# Gausss_pincond.net
KiCad netlist of a schematic drawn in EAGLE
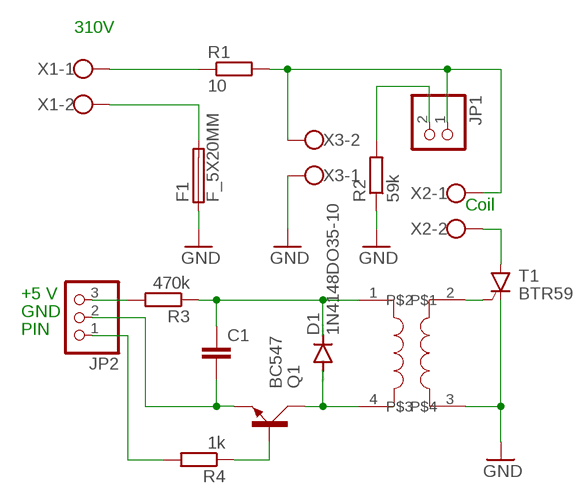
[diagram p0: schematic, sheet 1]

(export (version "E")
  (design (tool "Eeschema 10.0.6"))
  (components
    (comp (ref "C1")
      (value "C-EU025-025X050")
      (footprint "eagle-import:C025-025X050")
      (libsource (lib "eagle-import") (part "C-EU025-025X050"))
    )
    (comp (ref "D1")
      (value "1N4148DO35-10")
      (footprint "eagle-import:DO35-10")
      (libsource (lib "eagle-import") (part "1N4148DO35-10"))
    )
    (comp (ref "F1")
      (value "F_5X20MM")
      (footprint "eagle-import:FUSE_HOLDER_5X20MM")
      (libsource (lib "eagle-import") (part "FUSEBLANK_5X20MM"))
    )
    (comp (ref "JP1")
      (value "PINHD-1X2")
      (footprint "eagle-import:1X02")
      (libsource (lib "eagle-import") (part "PINHD-1X2"))
    )
    (comp (ref "JP2")
      (value "PINHD-1X3")
      (footprint "eagle-import:1X03")
      (libsource (lib "eagle-import") (part "PINHD-1X3"))
    )
    (comp (ref "Q1")
      (value "BC547")
      (footprint "eagle-import:SOT54A")
      (libsource (lib "eagle-import") (part "BC547"))
    )
    (comp (ref "R1")
      (value "10")
      (footprint "eagle-import:0207_10")
      (libsource (lib "eagle-import") (part "R-EU_0207/10"))
    )
    (comp (ref "R2")
      (value "59k")
      (footprint "eagle-import:0207_10")
      (libsource (lib "eagle-import") (part "R-EU_0207/10"))
    )
    (comp (ref "R3")
      (value "470k")
      (footprint "eagle-import:0207_10")
      (libsource (lib "eagle-import") (part "R-EU_0207/10"))
    )
    (comp (ref "R4")
      (value "1k")
      (footprint "eagle-import:0207_10")
      (libsource (lib "eagle-import") (part "R-EU_0207/10"))
    )
    (comp (ref "T1")
      (value "BTR59")
      (footprint "eagle-import:SOT93S")
      (libsource (lib "eagle-import") (part "BTR59"))
    )
    (comp (ref "U$2") (value "T") (footprint "eagle-import:SK11") (libsource (lib "eagle-import") (part "T")))
    (comp (ref "X1")
      (value "W237-102")
      (footprint "eagle-import:W237-102")
      (fields (field (name "MPN") "237-102"))
      (libsource (lib "eagle-import") (part "W237-102"))
    )
    (comp (ref "X2")
      (value "W237-102")
      (footprint "eagle-import:W237-102")
      (fields (field (name "MPN") "237-102"))
      (libsource (lib "eagle-import") (part "W237-102"))
    )
    (comp (ref "X3")
      (value "W237-102")
      (footprint "eagle-import:W237-102")
      (fields (field (name "MPN") "237-102"))
      (libsource (lib "eagle-import") (part "W237-102"))
    )
  )
  (nets
    (net (code "1") (name "GND") (class "Default")
      (node (ref "F1") (pin "1") (pinfunction "1_1") (pintype "passive"))
      (node (ref "R2") (pin "1") (pinfunction "1_1") (pintype "passive"))
      (node (ref "T1") (pin "C") (pinfunction "C_C") (pintype "passive"))
      (node (ref "U$2") (pin "3") (pinfunction "P$3_3") (pintype "bidirectional"))
      (node (ref "X3") (pin "1") (pinfunction "KL_1") (pintype "passive"))
    )
    (net (code "2") (name "Net-(C1-Pad2)") (class "Default")
      (node (ref "C1") (pin "2") (pinfunction "2_2") (pintype "passive"))
      (node (ref "JP2") (pin "2") (pinfunction "2_2") (pintype "passive"))
      (node (ref "Q1") (pin "E") (pinfunction "E_E") (pintype "passive"))
    )
    (net (code "3") (name "Net-(JP1-Pad2)") (class "Default")
      (node (ref "JP1") (pin "2") (pinfunction "2_2") (pintype "passive"))
      (node (ref "R2") (pin "2") (pinfunction "2_2") (pintype "passive"))
    )
    (net (code "4") (name "Net-(JP2-Pad1)") (class "Default")
      (node (ref "JP2") (pin "1") (pinfunction "1_1") (pintype "passive"))
      (node (ref "R4") (pin "2") (pinfunction "2_2") (pintype "passive"))
    )
    (net (code "5") (name "Net-(JP2-Pad3)") (class "Default")
      (node (ref "JP2") (pin "3") (pinfunction "3_3") (pintype "passive"))
      (node (ref "R3") (pin "2") (pinfunction "2_2") (pintype "passive"))
    )
    (net (code "6") (name "Net-(Q1-PadB)") (class "Default")
      (node (ref "Q1") (pin "B") (pinfunction "B_B") (pintype "passive"))
      (node (ref "R4") (pin "1") (pinfunction "1_1") (pintype "passive"))
    )
    (net (code "7") (name "Net-(U$2-P$1)") (class "Default")
      (node (ref "C1") (pin "1") (pinfunction "1_1") (pintype "passive"))
      (node (ref "D1") (pin "C") (pinfunction "C_C") (pintype "passive"))
      (node (ref "R3") (pin "1") (pinfunction "1_1") (pintype "passive"))
      (node (ref "U$2") (pin "1") (pinfunction "P$1_1") (pintype "bidirectional"))
    )
    (net (code "8") (name "Net-(U$2-P$2)") (class "Default")
      (node (ref "T1") (pin "G") (pinfunction "G_G") (pintype "passive"))
      (node (ref "U$2") (pin "2") (pinfunction "P$2_2") (pintype "bidirectional"))
    )
    (net (code "9") (name "Net-(U$2-P$4)") (class "Default")
      (node (ref "D1") (pin "A") (pinfunction "A_A") (pintype "passive"))
      (node (ref "Q1") (pin "C") (pinfunction "C_C") (pintype "passive"))
      (node (ref "U$2") (pin "4") (pinfunction "P$4_4") (pintype "bidirectional"))
    )
    (net (code "10") (name "Net-(X1A-KL)") (class "Default")
      (node (ref "R1") (pin "1") (pinfunction "1_1") (pintype "passive"))
      (node (ref "X1") (pin "1") (pinfunction "KL_1") (pintype "passive"))
    )
    (net (code "11") (name "Net-(X1B-KL)") (class "Default")
      (node (ref "F1") (pin "2") (pinfunction "2_2") (pintype "passive"))
      (node (ref "X1") (pin "2") (pinfunction "KL_2") (pintype "passive"))
    )
    (net (code "12") (name "Net-(X2A-KL)") (class "Default")
      (node (ref "JP1") (pin "1") (pinfunction "1_1") (pintype "passive"))
      (node (ref "R1") (pin "2") (pinfunction "2_2") (pintype "passive"))
      (node (ref "X2") (pin "1") (pinfunction "KL_1") (pintype "passive"))
      (node (ref "X3") (pin "2") (pinfunction "KL_2") (pintype "passive"))
    )
    (net (code "13") (name "Net-(X2B-KL)") (class "Default")
      (node (ref "T1") (pin "A") (pinfunction "A_A") (pintype "passive"))
      (node (ref "X2") (pin "2") (pinfunction "KL_2") (pintype "passive"))
    )
  )
)
